# mod_A.net
KiCad netlist of a schematic drawn in EAGLE
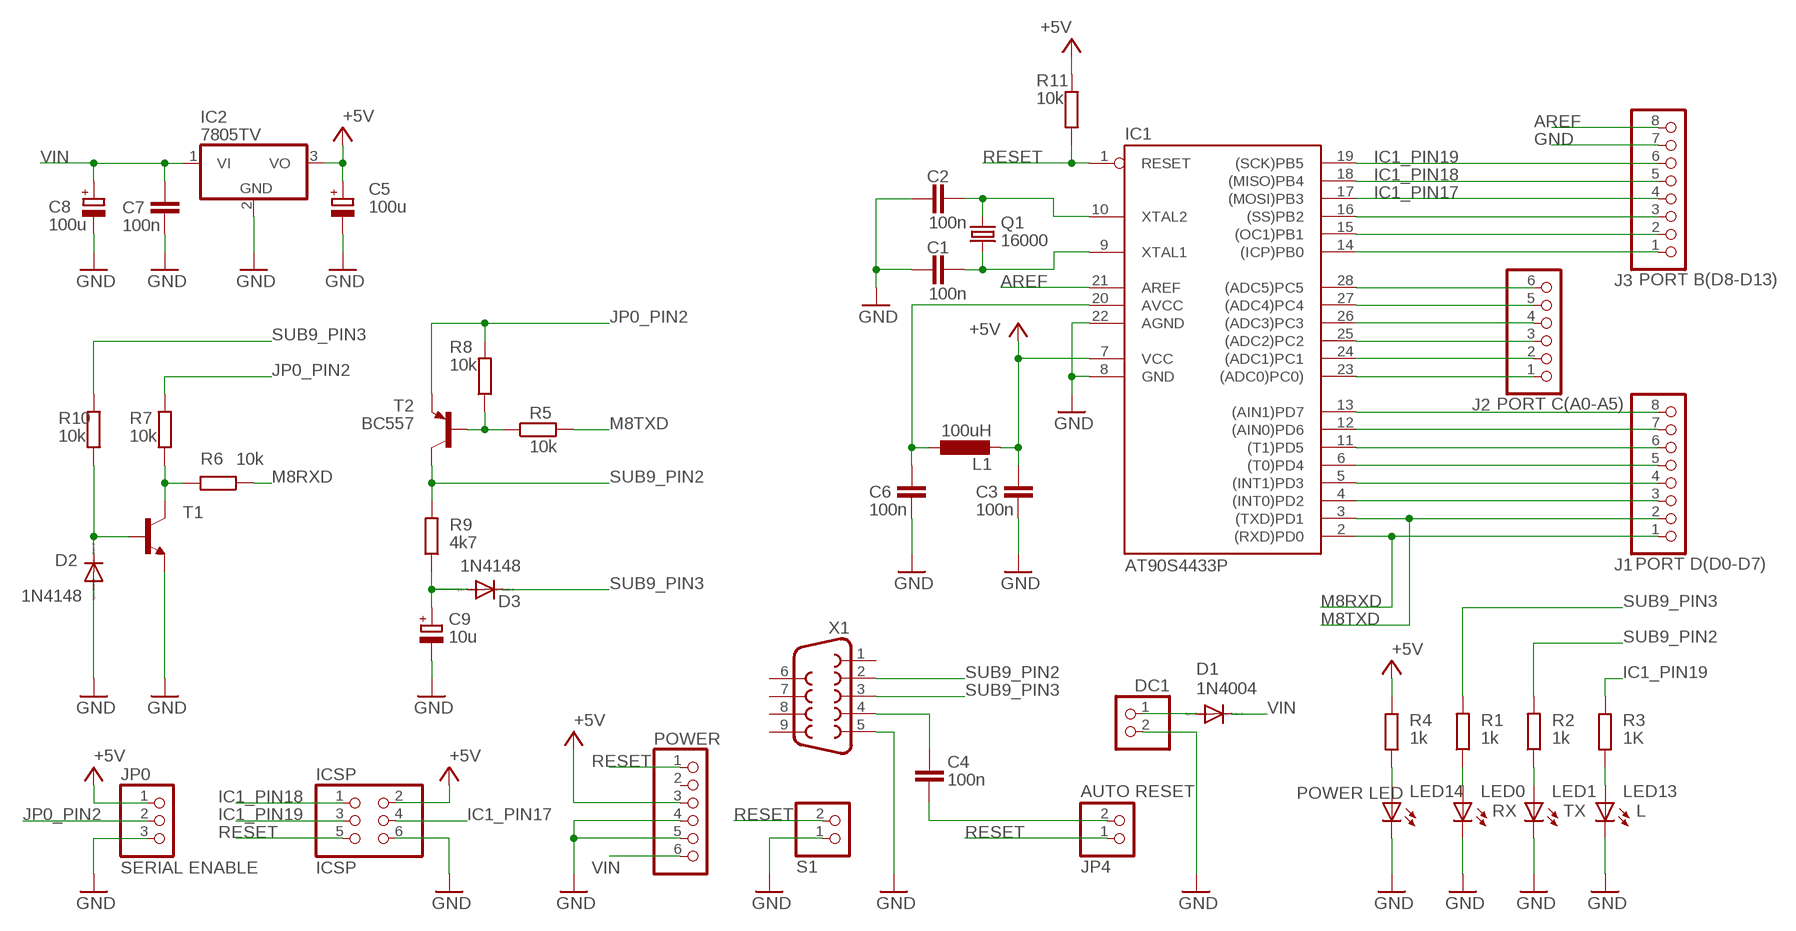
[diagram p0: schematic, sheet 1]

(export (version "E")
  (design (tool "Eeschema 10.0.6"))
  (components
    (comp (ref "C1")
      (value "100n")
      (footprint "eagle-import:C1206")
      (libsource (lib "eagle-import") (part "C-EUC1206"))
    )
    (comp (ref "C2")
      (value "100n")
      (footprint "eagle-import:C1206")
      (libsource (lib "eagle-import") (part "C-EUC1206"))
    )
    (comp (ref "C3")
      (value "100n")
      (footprint "eagle-import:C1206")
      (libsource (lib "eagle-import") (part "C-EUC1206"))
    )
    (comp (ref "C4")
      (value "100n")
      (footprint "eagle-import:C1206")
      (libsource (lib "eagle-import") (part "C-EUC1206"))
    )
    (comp (ref "C5")
      (value "100u")
      (footprint "eagle-import:E5-8,5")
      (libsource (lib "eagle-import") (part "CPOL-EUE5-8.5"))
    )
    (comp (ref "C6")
      (value "100n")
      (footprint "eagle-import:C1206")
      (libsource (lib "eagle-import") (part "C-EUC1206"))
    )
    (comp (ref "C7")
      (value "100n")
      (footprint "eagle-import:C1206")
      (libsource (lib "eagle-import") (part "C-EUC1206"))
    )
    (comp (ref "C8")
      (value "100u")
      (footprint "eagle-import:E5-8,5")
      (libsource (lib "eagle-import") (part "CPOL-EUE5-8.5"))
    )
    (comp (ref "C9")
      (value "10u")
      (footprint "eagle-import:SMC_B")
      (libsource (lib "eagle-import") (part "CPOL-EUSMCB"))
    )
    (comp (ref "D1")
      (value "1N4004")
      (footprint "eagle-import:DO41-10")
      (libsource (lib "eagle-import") (part "1N4004"))
    )
    (comp (ref "D2")
      (value "1N4148")
      (footprint "eagle-import:DO35-10")
      (libsource (lib "eagle-import") (part "1N4148DO35-10"))
    )
    (comp (ref "D3")
      (value "1N4148")
      (footprint "eagle-import:DO35-10")
      (libsource (lib "eagle-import") (part "1N4148DO35-10"))
    )
    (comp (ref "DC1")
      (value "PINHD-1X2")
      (footprint "eagle-import:1X02")
      (libsource (lib "eagle-import") (part "PINHD-1X2"))
    )
    (comp (ref "IC1")
      (value "AT90S4433P")
      (footprint "eagle-import:DIL28-3")
      (libsource (lib "eagle-import") (part "AT90S4433P"))
    )
    (comp (ref "IC2")
      (value "7805TV")
      (footprint "eagle-import:TO220V")
      (libsource (lib "eagle-import") (part "78TV05"))
    )
    (comp (ref "ICSP")
      (value "ICSP")
      (footprint "eagle-import:2X03")
      (libsource (lib "eagle-import") (part "PINHD-2X3"))
    )
    (comp (ref "J1")
      (value "PORT D(D0-D7)")
      (footprint "eagle-import:1X08")
      (libsource (lib "eagle-import") (part "PINHD-1X8"))
    )
    (comp (ref "J2")
      (value "PORT C(A0-A5)")
      (footprint "eagle-import:1X06")
      (libsource (lib "eagle-import") (part "PINHD-1X6"))
    )
    (comp (ref "J3")
      (value "PORT B(D8-D13)")
      (footprint "eagle-import:1X08")
      (libsource (lib "eagle-import") (part "PINHD-1X8"))
    )
    (comp (ref "JP0")
      (value "SERIAL ENABLE")
      (footprint "eagle-import:1X03")
      (libsource (lib "eagle-import") (part "PINHD-1X3"))
    )
    (comp (ref "JP4")
      (value "AUTO RESET")
      (footprint "eagle-import:1X02")
      (libsource (lib "eagle-import") (part "PINHD-1X2"))
    )
    (comp (ref "L1")
      (value "100uH")
      (footprint "eagle-import:L1812")
      (libsource (lib "eagle-import") (part "L-EUL1812"))
    )
    (comp (ref "LED0")
      (value "RX")
      (footprint "eagle-import:LED3MM")
      (libsource (lib "eagle-import") (part "LED3MM"))
    )
    (comp (ref "LED1")
      (value "TX")
      (footprint "eagle-import:LED3MM")
      (libsource (lib "eagle-import") (part "LED3MM"))
    )
    (comp (ref "LED13")
      (value "L")
      (footprint "eagle-import:LED3MM")
      (libsource (lib "eagle-import") (part "LED3MM"))
    )
    (comp (ref "LED14")
      (value "POWER LED")
      (footprint "eagle-import:LED3MM")
      (libsource (lib "eagle-import") (part "LED3MM"))
    )
    (comp (ref "POWER")
      (value "PINHD-1X6")
      (footprint "eagle-import:1X06")
      (libsource (lib "eagle-import") (part "PINHD-1X6"))
    )
    (comp (ref "Q1")
      (value "16000")
      (footprint "eagle-import:HC18U-V")
      (libsource (lib "eagle-import") (part "CRYSTALHC18U-V"))
    )
    (comp (ref "R1")
      (value "1k")
      (footprint "eagle-import:R1206")
      (libsource (lib "eagle-import") (part "R-EU_R1206"))
    )
    (comp (ref "R2")
      (value "1k")
      (footprint "eagle-import:R1206")
      (libsource (lib "eagle-import") (part "R-EU_R1206"))
    )
    (comp (ref "R3")
      (value "1K")
      (footprint "eagle-import:R1206")
      (libsource (lib "eagle-import") (part "R-EU_R1206"))
    )
    (comp (ref "R4")
      (value "1k")
      (footprint "eagle-import:R1206")
      (libsource (lib "eagle-import") (part "R-EU_R1206"))
    )
    (comp (ref "R5")
      (value "10k")
      (footprint "eagle-import:R1206")
      (libsource (lib "eagle-import") (part "R-EU_R1206"))
    )
    (comp (ref "R6")
      (value "10k")
      (footprint "eagle-import:R1206")
      (libsource (lib "eagle-import") (part "R-EU_R1206"))
    )
    (comp (ref "R7")
      (value "10k")
      (footprint "eagle-import:R1206")
      (libsource (lib "eagle-import") (part "R-EU_R1206"))
    )
    (comp (ref "R8")
      (value "10k")
      (footprint "eagle-import:R1206")
      (libsource (lib "eagle-import") (part "R-EU_R1206"))
    )
    (comp (ref "R9")
      (value "4k7")
      (footprint "eagle-import:R1206")
      (libsource (lib "eagle-import") (part "R-EU_R1206"))
    )
    (comp (ref "R10")
      (value "10k")
      (footprint "eagle-import:R1206")
      (libsource (lib "eagle-import") (part "R-EU_R1206"))
    )
    (comp (ref "R11")
      (value "10k")
      (footprint "eagle-import:R1206")
      (libsource (lib "eagle-import") (part "R-EU_R1206"))
    )
    (comp (ref "S1")
      (value "PINHD-1X2")
      (footprint "eagle-import:1X02")
      (libsource (lib "eagle-import") (part "PINHD-1X2"))
    )
    (comp (ref "T1")
      (value "BC547-NPN-TO92-CBE")
      (footprint "eagle-import:TO92-CBE")
      (libsource (lib "eagle-import") (part "-NPN-TO92-CBEBC547"))
    )
    (comp (ref "T2")
      (value "BC557")
      (footprint "eagle-import:TO92-EBC")
      (libsource (lib "eagle-import") (part "-PNP-TO92-EBCBC557B"))
    )
    (comp (ref "X1")
      (value "F09H")
      (footprint "eagle-import:F09H")
      (libsource (lib "eagle-import") (part "F09H"))
    )
  )
  (nets
    (net (code "1") (name "+5V") (class "Default")
      (node (ref "C3") (pin "1") (pinfunction "1_1") (pintype "passive"))
      (node (ref "C5") (pin "+") (pinfunction "+_+") (pintype "passive"))
      (node (ref "IC1") (pin "7") (pinfunction "VCC_7") (pintype "power_in"))
      (node (ref "IC2") (pin "3") (pinfunction "VO_3") (pintype "passive"))
      (node (ref "ICSP") (pin "2") (pinfunction "2_2") (pintype "passive"))
      (node (ref "JP0") (pin "1") (pinfunction "1_1") (pintype "passive"))
      (node (ref "L1") (pin "2") (pinfunction "2_2") (pintype "passive"))
      (node (ref "POWER") (pin "3") (pinfunction "3_3") (pintype "passive"))
      (node (ref "R11") (pin "2") (pinfunction "2_2") (pintype "passive"))
      (node (ref "R4") (pin "1") (pinfunction "1_1") (pintype "passive"))
    )
    (net (code "2") (name "/AREF") (class "Default")
      (node (ref "IC1") (pin "21") (pinfunction "AREF_21") (pintype "passive"))
      (node (ref "J3") (pin "8") (pinfunction "8_8") (pintype "passive"))
    )
    (net (code "3") (name "/IC1_PIN17") (class "Default")
      (node (ref "IC1") (pin "17") (pinfunction "(MOSI)PB3_17") (pintype "bidirectional"))
      (node (ref "ICSP") (pin "4") (pinfunction "4_4") (pintype "passive"))
      (node (ref "J3") (pin "4") (pinfunction "4_4") (pintype "passive"))
    )
    (net (code "4") (name "/IC1_PIN18") (class "Default")
      (node (ref "IC1") (pin "18") (pinfunction "(MISO)PB4_18") (pintype "bidirectional"))
      (node (ref "ICSP") (pin "1") (pinfunction "1_1") (pintype "passive"))
      (node (ref "J3") (pin "5") (pinfunction "5_5") (pintype "passive"))
    )
    (net (code "5") (name "/IC1_PIN19") (class "Default")
      (node (ref "IC1") (pin "19") (pinfunction "(SCK)PB5_19") (pintype "bidirectional"))
      (node (ref "ICSP") (pin "3") (pinfunction "3_3") (pintype "passive"))
      (node (ref "J3") (pin "6") (pinfunction "6_6") (pintype "passive"))
      (node (ref "R3") (pin "1") (pinfunction "1_1") (pintype "passive"))
    )
    (net (code "6") (name "/JP0_PIN2") (class "Default")
      (node (ref "JP0") (pin "2") (pinfunction "2_2") (pintype "passive"))
      (node (ref "R7") (pin "2") (pinfunction "2_2") (pintype "passive"))
      (node (ref "R8") (pin "2") (pinfunction "2_2") (pintype "passive"))
      (node (ref "T2") (pin "E") (pinfunction "E_E") (pintype "passive"))
    )
    (net (code "7") (name "/M8RXD") (class "Default")
      (node (ref "IC1") (pin "2") (pinfunction "(RXD)PD0_2") (pintype "bidirectional"))
      (node (ref "J1") (pin "1") (pinfunction "1_1") (pintype "passive"))
      (node (ref "R6") (pin "1") (pinfunction "1_1") (pintype "passive"))
    )
    (net (code "8") (name "/M8TXD") (class "Default")
      (node (ref "IC1") (pin "3") (pinfunction "(TXD)PD1_3") (pintype "bidirectional"))
      (node (ref "J1") (pin "2") (pinfunction "2_2") (pintype "passive"))
      (node (ref "R5") (pin "2") (pinfunction "2_2") (pintype "passive"))
    )
    (net (code "9") (name "/RESET") (class "Default")
      (node (ref "IC1") (pin "1") (pinfunction "RESET_1") (pintype "input"))
      (node (ref "ICSP") (pin "5") (pinfunction "5_5") (pintype "passive"))
      (node (ref "JP4") (pin "1") (pinfunction "1_1") (pintype "passive"))
      (node (ref "POWER") (pin "1") (pinfunction "1_1") (pintype "passive"))
      (node (ref "R11") (pin "1") (pinfunction "1_1") (pintype "passive"))
      (node (ref "S1") (pin "2") (pinfunction "2_2") (pintype "passive"))
    )
    (net (code "10") (name "/SUB9_PIN2") (class "Default")
      (node (ref "R2") (pin "2") (pinfunction "2_2") (pintype "passive"))
      (node (ref "R9") (pin "2") (pinfunction "2_2") (pintype "passive"))
      (node (ref "T2") (pin "C") (pinfunction "C_C") (pintype "passive"))
      (node (ref "X1") (pin "2") (pinfunction "2_2") (pintype "passive"))
    )
    (net (code "11") (name "/SUB9_PIN3") (class "Default")
      (node (ref "D3") (pin "C") (pinfunction "C_C") (pintype "passive"))
      (node (ref "R1") (pin "2") (pinfunction "2_2") (pintype "passive"))
      (node (ref "R10") (pin "2") (pinfunction "2_2") (pintype "passive"))
      (node (ref "X1") (pin "3") (pinfunction "3_3") (pintype "passive"))
    )
    (net (code "12") (name "/VIN") (class "Default")
      (node (ref "C7") (pin "1") (pinfunction "1_1") (pintype "passive"))
      (node (ref "C8") (pin "+") (pinfunction "+_+") (pintype "passive"))
      (node (ref "D1") (pin "C") (pinfunction "C_C") (pintype "passive"))
      (node (ref "IC2") (pin "1") (pinfunction "VI_1") (pintype "input"))
      (node (ref "POWER") (pin "6") (pinfunction "6_6") (pintype "passive"))
    )
    (net (code "13") (name "GND") (class "Default")
      (node (ref "C1") (pin "1") (pinfunction "1_1") (pintype "passive"))
      (node (ref "C2") (pin "1") (pinfunction "1_1") (pintype "passive"))
      (node (ref "C3") (pin "2") (pinfunction "2_2") (pintype "passive"))
      (node (ref "C5") (pin "-") (pinfunction "-_-") (pintype "passive"))
      (node (ref "C6") (pin "2") (pinfunction "2_2") (pintype "passive"))
      (node (ref "C7") (pin "2") (pinfunction "2_2") (pintype "passive"))
      (node (ref "C8") (pin "-") (pinfunction "-_-") (pintype "passive"))
      (node (ref "C9") (pin "-") (pinfunction "-_-") (pintype "passive"))
      (node (ref "D2") (pin "A") (pinfunction "A_A") (pintype "passive"))
      (node (ref "DC1") (pin "2") (pinfunction "2_2") (pintype "passive"))
      (node (ref "IC1") (pin "22") (pinfunction "AGND_22") (pintype "power_in"))
      (node (ref "IC1") (pin "8") (pinfunction "GND_8") (pintype "power_in"))
      (node (ref "IC2") (pin "2") (pinfunction "GND_2") (pintype "passive"))
      (node (ref "ICSP") (pin "6") (pinfunction "6_6") (pintype "passive"))
      (node (ref "J3") (pin "7") (pinfunction "7_7") (pintype "passive"))
      (node (ref "JP0") (pin "3") (pinfunction "3_3") (pintype "passive"))
      (node (ref "LED0") (pin "K") (pinfunction "C_K") (pintype "passive"))
      (node (ref "LED1") (pin "K") (pinfunction "C_K") (pintype "passive"))
      (node (ref "LED13") (pin "K") (pinfunction "C_K") (pintype "passive"))
      (node (ref "LED14") (pin "K") (pinfunction "C_K") (pintype "passive"))
      (node (ref "POWER") (pin "4") (pinfunction "4_4") (pintype "passive"))
      (node (ref "POWER") (pin "5") (pinfunction "5_5") (pintype "passive"))
      (node (ref "S1") (pin "1") (pinfunction "1_1") (pintype "passive"))
      (node (ref "T1") (pin "E") (pinfunction "E_E") (pintype "passive"))
      (node (ref "X1") (pin "5") (pinfunction "5_5") (pintype "passive"))
    )
    (net (code "14") (name "Net-(C4-Pad1)") (class "Default")
      (node (ref "C4") (pin "1") (pinfunction "1_1") (pintype "passive"))
      (node (ref "X1") (pin "4") (pinfunction "4_4") (pintype "passive"))
    )
    (net (code "15") (name "Net-(C4-Pad2)") (class "Default")
      (node (ref "C4") (pin "2") (pinfunction "2_2") (pintype "passive"))
      (node (ref "JP4") (pin "2") (pinfunction "2_2") (pintype "passive"))
    )
    (net (code "16") (name "Net-(C9-Pad+)") (class "Default")
      (node (ref "C9") (pin "+") (pinfunction "+_+") (pintype "passive"))
      (node (ref "D3") (pin "A") (pinfunction "A_A") (pintype "passive"))
      (node (ref "R9") (pin "1") (pinfunction "1_1") (pintype "passive"))
    )
    (net (code "17") (name "Net-(D1-PadA)") (class "Default")
      (node (ref "D1") (pin "A") (pinfunction "A_A") (pintype "passive"))
      (node (ref "DC1") (pin "1") (pinfunction "1_1") (pintype "passive"))
    )
    (net (code "18") (name "Net-(D2-PadC)") (class "Default")
      (node (ref "D2") (pin "C") (pinfunction "C_C") (pintype "passive"))
      (node (ref "R10") (pin "1") (pinfunction "1_1") (pintype "passive"))
      (node (ref "T1") (pin "B") (pinfunction "B_B") (pintype "passive"))
    )
    (net (code "19") (name "Net-(IC1-(ADC0)PC0))") (class "Default")
      (node (ref "IC1") (pin "23") (pinfunction "(ADC0)PC0)_23") (pintype "bidirectional"))
      (node (ref "J2") (pin "1") (pinfunction "1_1") (pintype "passive"))
    )
    (net (code "20") (name "Net-(IC1-(ADC1)PC1)") (class "Default")
      (node (ref "IC1") (pin "24") (pinfunction "(ADC1)PC1_24") (pintype "bidirectional"))
      (node (ref "J2") (pin "2") (pinfunction "2_2") (pintype "passive"))
    )
    (net (code "21") (name "Net-(IC1-(ADC2)PC2)") (class "Default")
      (node (ref "IC1") (pin "25") (pinfunction "(ADC2)PC2_25") (pintype "bidirectional"))
      (node (ref "J2") (pin "3") (pinfunction "3_3") (pintype "passive"))
    )
    (net (code "22") (name "Net-(IC1-(ADC3)PC3)") (class "Default")
      (node (ref "IC1") (pin "26") (pinfunction "(ADC3)PC3_26") (pintype "bidirectional"))
      (node (ref "J2") (pin "4") (pinfunction "4_4") (pintype "passive"))
    )
    (net (code "23") (name "Net-(IC1-(ADC4)PC4)") (class "Default")
      (node (ref "IC1") (pin "27") (pinfunction "(ADC4)PC4_27") (pintype "bidirectional"))
      (node (ref "J2") (pin "5") (pinfunction "5_5") (pintype "passive"))
    )
    (net (code "24") (name "Net-(IC1-(ADC5)PC5)") (class "Default")
      (node (ref "IC1") (pin "28") (pinfunction "(ADC5)PC5_28") (pintype "bidirectional"))
      (node (ref "J2") (pin "6") (pinfunction "6_6") (pintype "passive"))
    )
    (net (code "25") (name "Net-(IC1-(AIN0)PD6)") (class "Default")
      (node (ref "IC1") (pin "12") (pinfunction "(AIN0)PD6_12") (pintype "bidirectional"))
      (node (ref "J1") (pin "7") (pinfunction "7_7") (pintype "passive"))
    )
    (net (code "26") (name "Net-(IC1-(AIN1)PD7)") (class "Default")
      (node (ref "IC1") (pin "13") (pinfunction "(AIN1)PD7_13") (pintype "bidirectional"))
      (node (ref "J1") (pin "8") (pinfunction "8_8") (pintype "passive"))
    )
    (net (code "27") (name "Net-(IC1-(ICP)PB0)") (class "Default")
      (node (ref "IC1") (pin "14") (pinfunction "(ICP)PB0_14") (pintype "bidirectional"))
      (node (ref "J3") (pin "1") (pinfunction "1_1") (pintype "passive"))
    )
    (net (code "28") (name "Net-(IC1-(INT0)PD2)") (class "Default")
      (node (ref "IC1") (pin "4") (pinfunction "(INT0)PD2_4") (pintype "bidirectional"))
      (node (ref "J1") (pin "3") (pinfunction "3_3") (pintype "passive"))
    )
    (net (code "29") (name "Net-(IC1-(INT1)PD3)") (class "Default")
      (node (ref "IC1") (pin "5") (pinfunction "(INT1)PD3_5") (pintype "bidirectional"))
      (node (ref "J1") (pin "4") (pinfunction "4_4") (pintype "passive"))
    )
    (net (code "30") (name "Net-(IC1-(OC1)PB1)") (class "Default")
      (node (ref "IC1") (pin "15") (pinfunction "(OC1)PB1_15") (pintype "bidirectional"))
      (node (ref "J3") (pin "2") (pinfunction "2_2") (pintype "passive"))
    )
    (net (code "31") (name "Net-(IC1-(SS)PB2)") (class "Default")
      (node (ref "IC1") (pin "16") (pinfunction "(SS)PB2_16") (pintype "bidirectional"))
      (node (ref "J3") (pin "3") (pinfunction "3_3") (pintype "passive"))
    )
    (net (code "32") (name "Net-(IC1-(T0)PD4)") (class "Default")
      (node (ref "IC1") (pin "6") (pinfunction "(T0)PD4_6") (pintype "bidirectional"))
      (node (ref "J1") (pin "5") (pinfunction "5_5") (pintype "passive"))
    )
    (net (code "33") (name "Net-(IC1-(T1)PD5)") (class "Default")
      (node (ref "IC1") (pin "11") (pinfunction "(T1)PD5_11") (pintype "bidirectional"))
      (node (ref "J1") (pin "6") (pinfunction "6_6") (pintype "passive"))
    )
    (net (code "34") (name "Net-(IC1-AVCC)") (class "Default")
      (node (ref "C6") (pin "1") (pinfunction "1_1") (pintype "passive"))
      (node (ref "IC1") (pin "20") (pinfunction "AVCC_20") (pintype "power_in"))
      (node (ref "L1") (pin "1") (pinfunction "1_1") (pintype "passive"))
    )
    (net (code "35") (name "Net-(IC1-XTAL1)") (class "Default")
      (node (ref "C1") (pin "2") (pinfunction "2_2") (pintype "passive"))
      (node (ref "IC1") (pin "9") (pinfunction "XTAL1_9") (pintype "bidirectional"))
      (node (ref "Q1") (pin "1") (pinfunction "1_1") (pintype "passive"))
    )
    (net (code "36") (name "Net-(IC1-XTAL2)") (class "Default")
      (node (ref "C2") (pin "2") (pinfunction "2_2") (pintype "passive"))
      (node (ref "IC1") (pin "10") (pinfunction "XTAL2_10") (pintype "bidirectional"))
      (node (ref "Q1") (pin "2") (pinfunction "2_2") (pintype "passive"))
    )
    (net (code "37") (name "Net-(LED0-PadA)") (class "Default")
      (node (ref "LED0") (pin "A") (pinfunction "A_A") (pintype "passive"))
      (node (ref "R1") (pin "1") (pinfunction "1_1") (pintype "passive"))
    )
    (net (code "38") (name "Net-(LED1-PadA)") (class "Default")
      (node (ref "LED1") (pin "A") (pinfunction "A_A") (pintype "passive"))
      (node (ref "R2") (pin "1") (pinfunction "1_1") (pintype "passive"))
    )
    (net (code "39") (name "Net-(LED13-PadA)") (class "Default")
      (node (ref "LED13") (pin "A") (pinfunction "A_A") (pintype "passive"))
      (node (ref "R3") (pin "2") (pinfunction "2_2") (pintype "passive"))
    )
    (net (code "40") (name "Net-(LED14-PadA)") (class "Default")
      (node (ref "LED14") (pin "A") (pinfunction "A_A") (pintype "passive"))
      (node (ref "R4") (pin "2") (pinfunction "2_2") (pintype "passive"))
    )
    (net (code "41") (name "Net-(R5-Pad1)") (class "Default")
      (node (ref "R5") (pin "1") (pinfunction "1_1") (pintype "passive"))
      (node (ref "R8") (pin "1") (pinfunction "1_1") (pintype "passive"))
      (node (ref "T2") (pin "B") (pinfunction "B_B") (pintype "passive"))
    )
    (net (code "42") (name "Net-(R6-Pad2)") (class "Default")
      (node (ref "R6") (pin "2") (pinfunction "2_2") (pintype "passive"))
      (node (ref "R7") (pin "1") (pinfunction "1_1") (pintype "passive"))
      (node (ref "T1") (pin "C") (pinfunction "C_C") (pintype "passive"))
    )
    (net (code "43") (name "unconnected-(POWER-Pad2)") (class "Default")
      (node (ref "POWER") (pin "2") (pinfunction "2_2") (pintype "passive"))
    )
    (net (code "44") (name "unconnected-(X1-Pad1)") (class "Default")
      (node (ref "X1") (pin "1") (pinfunction "1_1") (pintype "passive"))
    )
    (net (code "45") (name "unconnected-(X1-Pad6)") (class "Default")
      (node (ref "X1") (pin "6") (pinfunction "6_6") (pintype "passive"))
    )
    (net (code "46") (name "unconnected-(X1-Pad7)") (class "Default")
      (node (ref "X1") (pin "7") (pinfunction "7_7") (pintype "passive"))
    )
    (net (code "47") (name "unconnected-(X1-Pad8)") (class "Default")
      (node (ref "X1") (pin "8") (pinfunction "8_8") (pintype "passive"))
    )
    (net (code "48") (name "unconnected-(X1-Pad9)") (class "Default")
      (node (ref "X1") (pin "9") (pinfunction "9_9") (pintype "passive"))
    )
  )
)
